# USB_HOST.net
KiCad netlist of a schematic drawn in Altium Designer
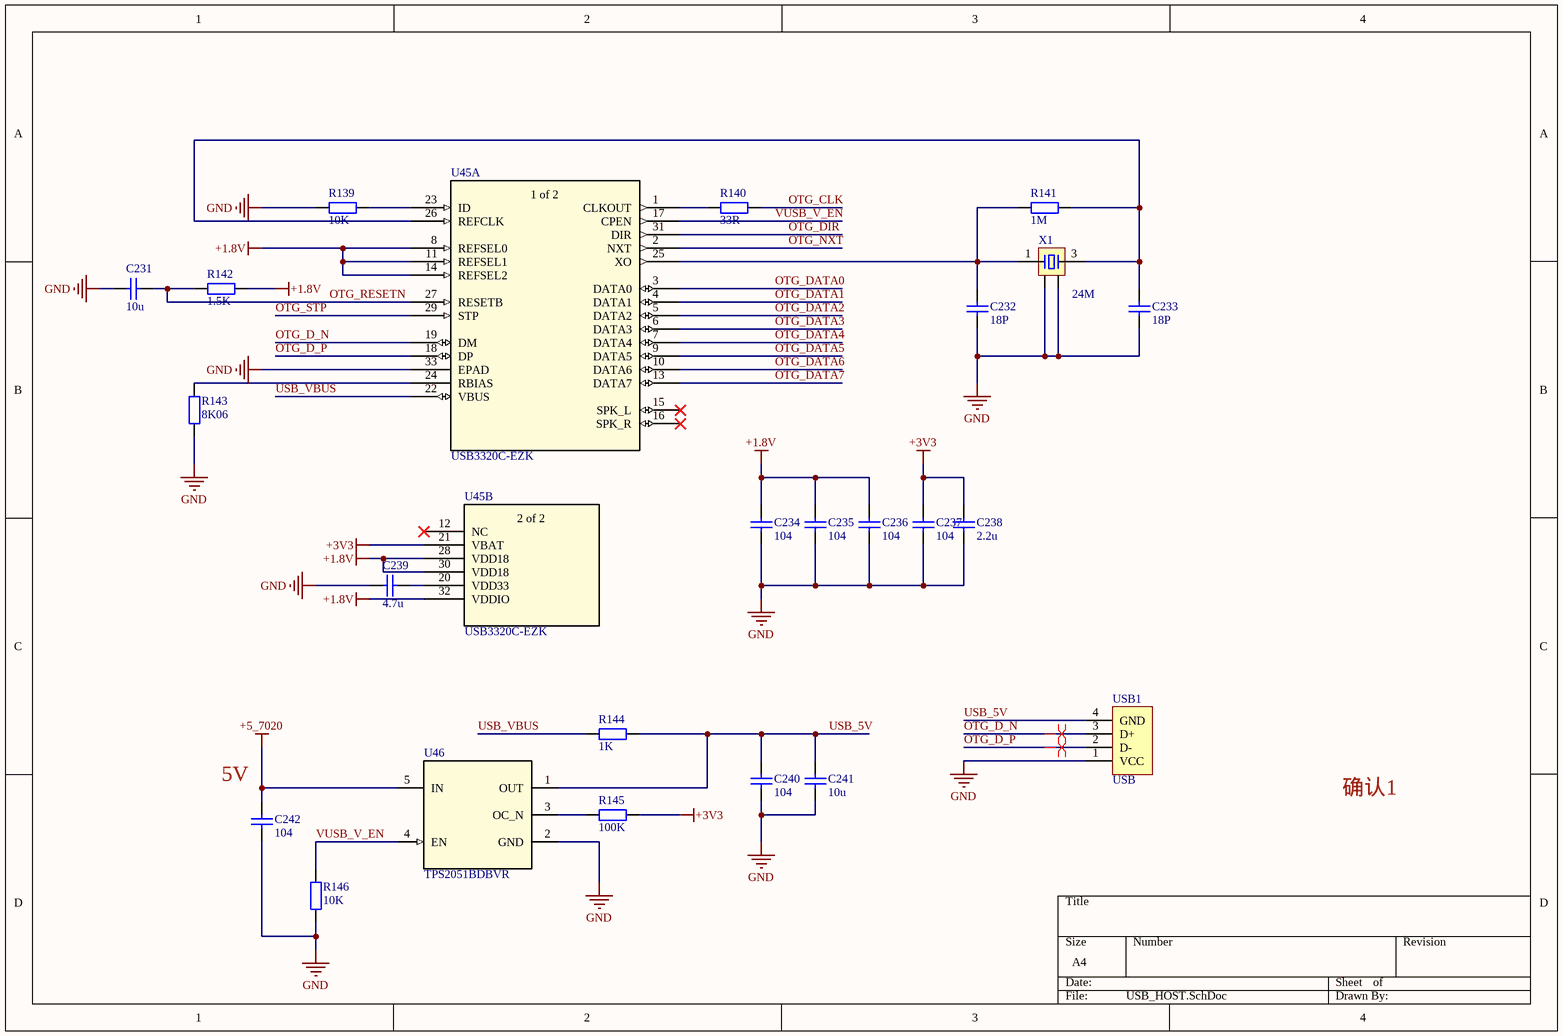
[diagram p0: USB_HOST.SchDoc]

(export (version "E")
  (design (tool "Eeschema 10.0.6"))
  (components
    (comp (ref "C231")
      (value "10u")
      (footprint "C0402_L")
      (description "贴片电容/MLCC电容")
      (libsource (lib "0.1 - 电阻-电容-电感-保险丝-晶振-晶体-磁珠-电位器-法拉电容-馈通电容") (part "C"))
    )
    (comp (ref "C232")
      (value "18P")
      (footprint "C0402_L")
      (description "贴片电容/MLCC电容")
      (libsource (lib "0.1 - 电阻-电容-电感-保险丝-晶振-晶体-磁珠-电位器-法拉电容-馈通电容") (part "C"))
    )
    (comp (ref "C233")
      (value "18P")
      (footprint "C0402_L")
      (description "贴片电容/MLCC电容")
      (libsource (lib "0.1 - 电阻-电容-电感-保险丝-晶振-晶体-磁珠-电位器-法拉电容-馈通电容") (part "C"))
    )
    (comp (ref "C234")
      (value "104")
      (footprint "C0402_L")
      (description "贴片电容/MLCC电容")
      (libsource (lib "0.1 - 电阻-电容-电感-保险丝-晶振-晶体-磁珠-电位器-法拉电容-馈通电容") (part "C"))
    )
    (comp (ref "C235")
      (value "104")
      (footprint "C0402_L")
      (description "贴片电容/MLCC电容")
      (libsource (lib "0.1 - 电阻-电容-电感-保险丝-晶振-晶体-磁珠-电位器-法拉电容-馈通电容") (part "C"))
    )
    (comp (ref "C236")
      (value "104")
      (footprint "C0402_L")
      (description "贴片电容/MLCC电容")
      (libsource (lib "0.1 - 电阻-电容-电感-保险丝-晶振-晶体-磁珠-电位器-法拉电容-馈通电容") (part "C"))
    )
    (comp (ref "C237")
      (value "104")
      (footprint "C0402_L")
      (description "贴片电容/MLCC电容")
      (libsource (lib "0.1 - 电阻-电容-电感-保险丝-晶振-晶体-磁珠-电位器-法拉电容-馈通电容") (part "C"))
    )
    (comp (ref "C238")
      (value "2.2u")
      (footprint "C0402_L")
      (description "贴片电容/MLCC电容")
      (libsource (lib "0.1 - 电阻-电容-电感-保险丝-晶振-晶体-磁珠-电位器-法拉电容-馈通电容") (part "C"))
    )
    (comp (ref "C239")
      (value "4.7u")
      (footprint "C0402_L")
      (description "贴片电容/MLCC电容")
      (libsource (lib "0.1 - 电阻-电容-电感-保险丝-晶振-晶体-磁珠-电位器-法拉电容-馈通电容") (part "C"))
    )
    (comp (ref "C240")
      (value "104")
      (footprint "C0402_L")
      (description "贴片电容/MLCC电容")
      (libsource (lib "0.1 - 电阻-电容-电感-保险丝-晶振-晶体-磁珠-电位器-法拉电容-馈通电容") (part "C"))
    )
    (comp (ref "C241")
      (value "10u")
      (footprint "C0402_L")
      (description "贴片电容/MLCC电容")
      (libsource (lib "0.1 - 电阻-电容-电感-保险丝-晶振-晶体-磁珠-电位器-法拉电容-馈通电容") (part "C"))
    )
    (comp (ref "C242")
      (value "104")
      (footprint "C0402_L")
      (description "贴片电容/MLCC电容")
      (libsource (lib "0.1 - 电阻-电容-电感-保险丝-晶振-晶体-磁珠-电位器-法拉电容-馈通电容") (part "C"))
    )
    (comp (ref "R139")
      (value "10K")
      (footprint "R0402_L")
      (description "贴片电阻")
      (libsource (lib "0.1 - 电阻-电容-电感-保险丝-晶振-晶体-磁珠-电位器-法拉电容-馈通电容") (part "R"))
    )
    (comp (ref "R140")
      (value "33R")
      (footprint "R0402_L")
      (description "贴片电阻")
      (libsource (lib "0.1 - 电阻-电容-电感-保险丝-晶振-晶体-磁珠-电位器-法拉电容-馈通电容") (part "R"))
    )
    (comp (ref "R141")
      (value "1M")
      (footprint "R0402_L")
      (description "贴片电阻")
      (libsource (lib "0.1 - 电阻-电容-电感-保险丝-晶振-晶体-磁珠-电位器-法拉电容-馈通电容") (part "R"))
    )
    (comp (ref "R142")
      (value "1.5K")
      (footprint "R0402_L")
      (description "贴片电阻")
      (libsource (lib "0.1 - 电阻-电容-电感-保险丝-晶振-晶体-磁珠-电位器-法拉电容-馈通电容") (part "R"))
    )
    (comp (ref "R143")
      (value "8K06")
      (footprint "R0402_L")
      (description "贴片电阻")
      (libsource (lib "0.1 - 电阻-电容-电感-保险丝-晶振-晶体-磁珠-电位器-法拉电容-馈通电容") (part "R"))
    )
    (comp (ref "R144")
      (value "1K")
      (footprint "R0402_L")
      (description "贴片电阻")
      (libsource (lib "0.1 - 电阻-电容-电感-保险丝-晶振-晶体-磁珠-电位器-法拉电容-馈通电容") (part "R"))
    )
    (comp (ref "R145")
      (value "100K")
      (footprint "R0402_L")
      (description "贴片电阻")
      (libsource (lib "0.1 - 电阻-电容-电感-保险丝-晶振-晶体-磁珠-电位器-法拉电容-馈通电容") (part "R"))
    )
    (comp (ref "R146")
      (value "10K")
      (footprint "R0402_L")
      (description "贴片电阻")
      (libsource (lib "0.1 - 电阻-电容-电感-保险丝-晶振-晶体-磁珠-电位器-法拉电容-馈通电容") (part "R"))
    )
    (comp (ref "U45")
      (value "USB3320C-EZK")
      (footprint "QFN32_5X5MC_MCH")
      (description "No Description Available")
      (libsource (lib "USB3320C-EZK") (part "USB3320C-EZK"))
    )
    (comp (ref "U46")
      (value "TPS2051BDBVR")
      (footprint "DBV0005A_N")
      (description "No Description Available")
      (fields
        (field (name "ALTERNATE_PARTNUMBER") "TPS2051BDBVT")
        (field (name "MANUFACTURER") "Texas Instruments")
      )
      (libsource (lib "TPS2051BDBVR") (part "TPS2051BDBVR"))
    )
    (comp (ref "USB1")
      (value "USB")
      (footprint "USB2.0_Type-A_DIP_F_3")
      (description "USB2.0_Type-A母座")
      (libsource (lib "0.6 - 电源_音频_USB Type-C_HDMI_XT60_5557_D-SUB_RJ45_SD-TF_SIM插座") (part "USB2.0_Type-A_F"))
    )
    (comp (ref "X1")
      (value "24M")
      (footprint "XTAL-2025-4P")
      (description "4脚无源晶振(谐振器）")
      (libsource (lib "0.1 - 电阻-电容-电感-保险丝-晶振-晶体-磁珠-电位器-法拉电容-馈通电容") (part "XTAL-4P"))
    )
  )
  (nets
    (net (code "1") (name "+1.8V") (class "Default")
      (node (ref "C234") (pin "2") (pinfunction "2_2") (pintype "passive"))
      (node (ref "C235") (pin "2") (pinfunction "2_2") (pintype "passive"))
      (node (ref "C236") (pin "2") (pinfunction "2_2") (pintype "passive"))
      (node (ref "R142") (pin "2") (pinfunction "2_2") (pintype "passive"))
      (node (ref "U45") (pin "11") (pinfunction "REFSEL1_11") (pintype "input"))
      (node (ref "U45") (pin "14") (pinfunction "REFSEL2_14") (pintype "input"))
      (node (ref "U45") (pin "28") (pinfunction "VDD18_28") (pintype "power_in"))
      (node (ref "U45") (pin "30") (pinfunction "VDD18_30") (pintype "power_in"))
      (node (ref "U45") (pin "32") (pinfunction "VDDIO_32") (pintype "power_in"))
      (node (ref "U45") (pin "8") (pinfunction "REFSEL0_8") (pintype "input"))
    )
    (net (code "2") (name "+3V3") (class "Default")
      (node (ref "C237") (pin "2") (pinfunction "2_2") (pintype "passive"))
      (node (ref "C238") (pin "2") (pinfunction "2_2") (pintype "passive"))
      (node (ref "R145") (pin "1") (pinfunction "1_1") (pintype "passive"))
      (node (ref "U45") (pin "21") (pinfunction "VBAT_21") (pintype "power_in"))
    )
    (net (code "3") (name "+5_7020") (class "Default")
      (node (ref "C242") (pin "2") (pinfunction "2_2") (pintype "passive"))
      (node (ref "U46") (pin "5") (pinfunction "IN_5") (pintype "power_in"))
    )
    (net (code "4") (name "/OTG_CLK") (class "Default")
      (node (ref "R140") (pin "1") (pinfunction "1_1") (pintype "passive"))
    )
    (net (code "5") (name "/OTG_DATA0") (class "Default")
      (node (ref "U45") (pin "3") (pinfunction "DATA0_3") (pintype "bidirectional"))
    )
    (net (code "6") (name "/OTG_DATA1") (class "Default")
      (node (ref "U45") (pin "4") (pinfunction "DATA1_4") (pintype "bidirectional"))
    )
    (net (code "7") (name "/OTG_DATA2") (class "Default")
      (node (ref "U45") (pin "5") (pinfunction "DATA2_5") (pintype "bidirectional"))
    )
    (net (code "8") (name "/OTG_DATA3") (class "Default")
      (node (ref "U45") (pin "6") (pinfunction "DATA3_6") (pintype "bidirectional"))
    )
    (net (code "9") (name "/OTG_DATA4") (class "Default")
      (node (ref "U45") (pin "7") (pinfunction "DATA4_7") (pintype "bidirectional"))
    )
    (net (code "10") (name "/OTG_DATA5") (class "Default")
      (node (ref "U45") (pin "9") (pinfunction "DATA5_9") (pintype "bidirectional"))
    )
    (net (code "11") (name "/OTG_DATA6") (class "Default")
      (node (ref "U45") (pin "10") (pinfunction "DATA6_10") (pintype "bidirectional"))
    )
    (net (code "12") (name "/OTG_DATA7") (class "Default")
      (node (ref "U45") (pin "13") (pinfunction "DATA7_13") (pintype "bidirectional"))
    )
    (net (code "13") (name "/OTG_DIR") (class "Default")
      (node (ref "U45") (pin "31") (pinfunction "DIR_31") (pintype "output"))
    )
    (net (code "14") (name "/OTG_D_N") (class "Default")
      (node (ref "U45") (pin "19") (pinfunction "DM_19") (pintype "bidirectional"))
      (node (ref "USB1") (pin "3") (pinfunction "D+_3") (pintype "passive"))
    )
    (net (code "15") (name "/OTG_D_P") (class "Default")
      (node (ref "U45") (pin "18") (pinfunction "DP_18") (pintype "bidirectional"))
      (node (ref "USB1") (pin "2") (pinfunction "D-_2") (pintype "passive"))
    )
    (net (code "16") (name "/OTG_NXT") (class "Default")
      (node (ref "U45") (pin "2") (pinfunction "NXT_2") (pintype "output"))
    )
    (net (code "17") (name "/OTG_RESETN") (class "Default")
      (node (ref "C231") (pin "2") (pinfunction "2_2") (pintype "passive"))
      (node (ref "R142") (pin "1") (pinfunction "1_1") (pintype "passive"))
      (node (ref "U45") (pin "27") (pinfunction "RESETB_27") (pintype "input"))
    )
    (net (code "18") (name "/OTG_STP") (class "Default")
      (node (ref "U45") (pin "29") (pinfunction "STP_29") (pintype "input"))
    )
    (net (code "19") (name "/USB_5V") (class "Default")
      (node (ref "C240") (pin "2") (pinfunction "2_2") (pintype "passive"))
      (node (ref "C241") (pin "2") (pinfunction "2_2") (pintype "passive"))
      (node (ref "R144") (pin "1") (pinfunction "1_1") (pintype "passive"))
      (node (ref "U46") (pin "1") (pinfunction "OUT_1") (pintype "power_in"))
      (node (ref "USB1") (pin "4") (pinfunction "GND_4") (pintype "passive"))
    )
    (net (code "20") (name "/USB_VBUS") (class "Default")
      (node (ref "R144") (pin "2") (pinfunction "2_2") (pintype "passive"))
      (node (ref "U45") (pin "22") (pinfunction "VBUS_22") (pintype "bidirectional"))
    )
    (net (code "21") (name "/VUSB_V_EN") (class "Default")
      (node (ref "R146") (pin "1") (pinfunction "1_1") (pintype "passive"))
      (node (ref "U45") (pin "17") (pinfunction "CPEN_17") (pintype "output"))
      (node (ref "U46") (pin "4") (pinfunction "EN_4") (pintype "input"))
    )
    (net (code "22") (name "GND") (class "Default")
      (node (ref "C231") (pin "1") (pinfunction "1_1") (pintype "passive"))
      (node (ref "C232") (pin "1") (pinfunction "1_1") (pintype "passive"))
      (node (ref "C233") (pin "1") (pinfunction "1_1") (pintype "passive"))
      (node (ref "C234") (pin "1") (pinfunction "1_1") (pintype "passive"))
      (node (ref "C235") (pin "1") (pinfunction "1_1") (pintype "passive"))
      (node (ref "C236") (pin "1") (pinfunction "1_1") (pintype "passive"))
      (node (ref "C237") (pin "1") (pinfunction "1_1") (pintype "passive"))
      (node (ref "C238") (pin "1") (pinfunction "1_1") (pintype "passive"))
      (node (ref "C239") (pin "1") (pinfunction "1_1") (pintype "passive"))
      (node (ref "C240") (pin "1") (pinfunction "1_1") (pintype "passive"))
      (node (ref "C241") (pin "1") (pinfunction "1_1") (pintype "passive"))
      (node (ref "C242") (pin "1") (pinfunction "1_1") (pintype "passive"))
      (node (ref "R139") (pin "2") (pinfunction "2_2") (pintype "passive"))
      (node (ref "R143") (pin "1") (pinfunction "1_1") (pintype "passive"))
      (node (ref "R146") (pin "2") (pinfunction "2_2") (pintype "passive"))
      (node (ref "U45") (pin "33") (pinfunction "EPAD_33") (pintype "passive"))
      (node (ref "U46") (pin "2") (pinfunction "GND_2") (pintype "power_in"))
      (node (ref "USB1") (pin "1") (pinfunction "VCC_1") (pintype "passive"))
      (node (ref "X1") (pin "2") (pinfunction "2_2") (pintype "passive"))
      (node (ref "X1") (pin "4") (pinfunction "4_4") (pintype "passive"))
    )
    (net (code "23") (name "Net-(U45A-CLKOUT)") (class "Default")
      (node (ref "R140") (pin "2") (pinfunction "2_2") (pintype "passive"))
      (node (ref "U45") (pin "1") (pinfunction "CLKOUT_1") (pintype "output"))
    )
    (net (code "24") (name "Net-(U45A-ID)") (class "Default")
      (node (ref "R139") (pin "1") (pinfunction "1_1") (pintype "passive"))
      (node (ref "U45") (pin "23") (pinfunction "ID_23") (pintype "input"))
    )
    (net (code "25") (name "Net-(U45A-RBIAS)") (class "Default")
      (node (ref "R143") (pin "2") (pinfunction "2_2") (pintype "passive"))
      (node (ref "U45") (pin "24") (pinfunction "RBIAS_24") (pintype "passive"))
    )
    (net (code "26") (name "Net-(U45A-REFCLK)") (class "Default")
      (node (ref "C233") (pin "2") (pinfunction "2_2") (pintype "passive"))
      (node (ref "R141") (pin "1") (pinfunction "1_1") (pintype "passive"))
      (node (ref "U45") (pin "26") (pinfunction "REFCLK_26") (pintype "input"))
      (node (ref "X1") (pin "3") (pinfunction "3_3") (pintype "passive"))
    )
    (net (code "27") (name "Net-(U45A-XO)") (class "Default")
      (node (ref "C232") (pin "2") (pinfunction "2_2") (pintype "passive"))
      (node (ref "R141") (pin "2") (pinfunction "2_2") (pintype "passive"))
      (node (ref "U45") (pin "25") (pinfunction "XO_25") (pintype "output"))
      (node (ref "X1") (pin "1") (pinfunction "1_1") (pintype "passive"))
    )
    (net (code "28") (name "Net-(U45B-VDD33)") (class "Default")
      (node (ref "C239") (pin "2") (pinfunction "2_2") (pintype "passive"))
      (node (ref "U45") (pin "20") (pinfunction "VDD33_20") (pintype "power_in"))
    )
    (net (code "29") (name "Net-(U46-OC_N)") (class "Default")
      (node (ref "R145") (pin "2") (pinfunction "2_2") (pintype "passive"))
      (node (ref "U46") (pin "3") (pinfunction "OC_N_3") (pintype "open_collector"))
    )
    (net (code "30") (name "unconnected-(U45A-SPK_L-Pad15)") (class "Default")
      (node (ref "U45") (pin "15") (pinfunction "SPK_L_15") (pintype "bidirectional+no_connect"))
    )
    (net (code "31") (name "unconnected-(U45A-SPK_R-Pad16)") (class "Default")
      (node (ref "U45") (pin "16") (pinfunction "SPK_R_16") (pintype "bidirectional+no_connect"))
    )
    (net (code "32") (name "unconnected-(U45B-NC-Pad12)") (class "Default")
      (node (ref "U45") (pin "12") (pinfunction "NC_12") (pintype "passive+no_connect"))
    )
  )
)
